# Schaltplan.net
KiCad netlist of a schematic drawn in EAGLE
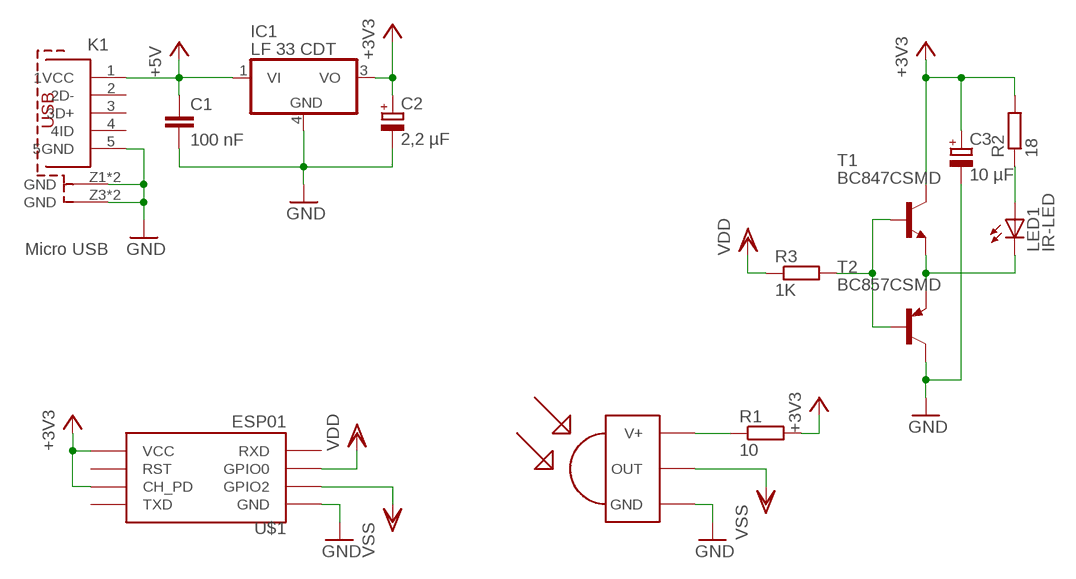
[diagram p0: schematic, sheet 1]

(export (version "E")
  (design (tool "Eeschema 10.0.6"))
  (components
    (comp (ref "C1")
      (value "100 nF")
      (footprint "eagle-import:C0805K")
      (libsource (lib "eagle-import") (part "C-EUC0805K"))
    )
    (comp (ref "C2")
      (value "2,2 µF")
      (footprint "eagle-import:E2,5-5")
      (libsource (lib "eagle-import") (part "CPOL-EUE2.5-5"))
    )
    (comp (ref "C3")
      (value "10 µF")
      (footprint "eagle-import:E2,5-5")
      (libsource (lib "eagle-import") (part "CPOL-EUE2.5-5"))
    )
    (comp (ref "IC1")
      (value "LF 33 CDT")
      (footprint "eagle-import:DPACK_3")
      (libsource (lib "eagle-import") (part "MC78M05ABDT"))
    )
    (comp (ref "IR-TRANSMITTER")
      (value "TSOP1833")
      (footprint "eagle-import:TSOP18XX")
      (libsource (lib "eagle-import") (part "TSOP1833"))
    )
    (comp (ref "K1")
      (value "Micro USB")
      (footprint "eagle-import:629105150521")
      (libsource (lib "eagle-import") (part "629105150521"))
    )
    (comp (ref "LED1")
      (value "IR-LED")
      (footprint "eagle-import:LED5MM")
      (libsource (lib "eagle-import") (part "LED5MM"))
    )
    (comp (ref "R1")
      (value "10")
      (footprint "eagle-import:M0805")
      (libsource (lib "eagle-import") (part "R-EU_M0805"))
    )
    (comp (ref "R2")
      (value "18")
      (footprint "eagle-import:M0805")
      (libsource (lib "eagle-import") (part "R-EU_M0805"))
    )
    (comp (ref "R3")
      (value "1K")
      (footprint "eagle-import:M0805")
      (libsource (lib "eagle-import") (part "R-EU_M0805"))
    )
    (comp (ref "T1")
      (value "BC847CSMD")
      (footprint "eagle-import:SOT23")
      (libsource (lib "eagle-import") (part "BC847SMDC"))
    )
    (comp (ref "T2")
      (value "BC857CSMD")
      (footprint "eagle-import:SOT23-BEC")
      (libsource (lib "eagle-import") (part "BC857SMDC"))
    )
    (comp (ref "U$1")
      (value "ESP01")
      (footprint "eagle-import:ESP01")
      (libsource (lib "eagle-import") (part "ESP01"))
    )
  )
  (nets
    (net (code "1") (name "+3V3") (class "Default")
      (node (ref "C2") (pin "+") (pinfunction "+_+") (pintype "passive"))
      (node (ref "C3") (pin "+") (pinfunction "+_+") (pintype "passive"))
      (node (ref "IC1") (pin "3") (pinfunction "VO_3") (pintype "passive"))
      (node (ref "R1") (pin "2") (pinfunction "2_2") (pintype "passive"))
      (node (ref "R2") (pin "2") (pinfunction "2_2") (pintype "passive"))
      (node (ref "T1") (pin "3") (pinfunction "C_3") (pintype "passive"))
      (node (ref "U$1") (pin "CH_PD") (pinfunction "CH_PD_CH_PD") (pintype "bidirectional"))
      (node (ref "U$1") (pin "VCC") (pinfunction "VCC_VCC") (pintype "bidirectional"))
    )
    (net (code "2") (name "+5V") (class "Default")
      (node (ref "C1") (pin "1") (pinfunction "1_1") (pintype "passive"))
      (node (ref "IC1") (pin "1") (pinfunction "VI_1") (pintype "input"))
      (node (ref "K1") (pin "1") (pinfunction "1VCC_1") (pintype "passive"))
    )
    (net (code "3") (name "GND") (class "Default")
      (node (ref "C1") (pin "2") (pinfunction "2_2") (pintype "passive"))
      (node (ref "C2") (pin "-") (pinfunction "-_-") (pintype "passive"))
      (node (ref "C3") (pin "-") (pinfunction "-_-") (pintype "passive"))
      (node (ref "IC1") (pin "4") (pinfunction "GND_4") (pintype "passive"))
      (node (ref "IR-TRANSMITTER") (pin "GND") (pinfunction "GND_GND") (pintype "bidirectional"))
      (node (ref "K1") (pin "5") (pinfunction "5GND_5") (pintype "passive"))
      (node (ref "K1") (pin "Z1") (pinfunction "GND_Z1") (pintype "bidirectional"))
      (node (ref "K1") (pin "Z2") (pinfunction "GND_Z2") (pintype "bidirectional"))
      (node (ref "K1") (pin "Z3") (pinfunction "GND_Z3") (pintype "bidirectional"))
      (node (ref "K1") (pin "Z4") (pinfunction "GND_Z4") (pintype "bidirectional"))
      (node (ref "T2") (pin "C") (pinfunction "C_C") (pintype "passive"))
      (node (ref "U$1") (pin "GND") (pinfunction "GND_GND") (pintype "bidirectional"))
    )
    (net (code "4") (name "Net-(IR-TRANSMITTER-V+)") (class "Default")
      (node (ref "IR-TRANSMITTER") (pin "VCC") (pinfunction "V+_VCC") (pintype "bidirectional"))
      (node (ref "R1") (pin "1") (pinfunction "1_1") (pintype "passive"))
    )
    (net (code "5") (name "Net-(LED1-C)") (class "Default")
      (node (ref "LED1") (pin "K") (pinfunction "C_K") (pintype "passive"))
      (node (ref "T1") (pin "2") (pinfunction "E_2") (pintype "passive"))
      (node (ref "T2") (pin "E") (pinfunction "E_E") (pintype "passive"))
    )
    (net (code "6") (name "Net-(LED1-PadA)") (class "Default")
      (node (ref "LED1") (pin "A") (pinfunction "A_A") (pintype "passive"))
      (node (ref "R2") (pin "1") (pinfunction "1_1") (pintype "passive"))
    )
    (net (code "7") (name "Net-(T1-B)") (class "Default")
      (node (ref "R3") (pin "2") (pinfunction "2_2") (pintype "passive"))
      (node (ref "T1") (pin "1") (pinfunction "B_1") (pintype "passive"))
      (node (ref "T2") (pin "B") (pinfunction "B_B") (pintype "passive"))
    )
    (net (code "8") (name "VDD") (class "Default")
      (node (ref "R3") (pin "1") (pinfunction "1_1") (pintype "passive"))
      (node (ref "U$1") (pin "GPIO0") (pinfunction "GPIO0_GPIO0") (pintype "bidirectional"))
    )
    (net (code "9") (name "VSS") (class "Default")
      (node (ref "IR-TRANSMITTER") (pin "OUT") (pinfunction "OUT_OUT") (pintype "bidirectional"))
      (node (ref "U$1") (pin "GPIO2") (pinfunction "GPIO2_GPIO2") (pintype "bidirectional"))
    )
    (net (code "10") (name "unconnected-(K1-2D--Pad2)") (class "Default")
      (node (ref "K1") (pin "2") (pinfunction "2D-_2") (pintype "passive"))
    )
    (net (code "11") (name "unconnected-(K1-3D+-Pad3)") (class "Default")
      (node (ref "K1") (pin "3") (pinfunction "3D+_3") (pintype "passive"))
    )
    (net (code "12") (name "unconnected-(K1-4ID-Pad4)") (class "Default")
      (node (ref "K1") (pin "4") (pinfunction "4ID_4") (pintype "passive"))
    )
    (net (code "13") (name "unconnected-(U$1-PadRST)") (class "Default")
      (node (ref "U$1") (pin "RST") (pinfunction "RST_RST") (pintype "bidirectional"))
    )
    (net (code "14") (name "unconnected-(U$1-RXD-PadRX)") (class "Default")
      (node (ref "U$1") (pin "RX") (pinfunction "RXD_RX") (pintype "bidirectional"))
    )
    (net (code "15") (name "unconnected-(U$1-TXD-PadTX)") (class "Default")
      (node (ref "U$1") (pin "TX") (pinfunction "TXD_TX") (pintype "bidirectional"))
    )
  )
)
